# SMPS.net
KiCad netlist of a schematic drawn in EAGLE
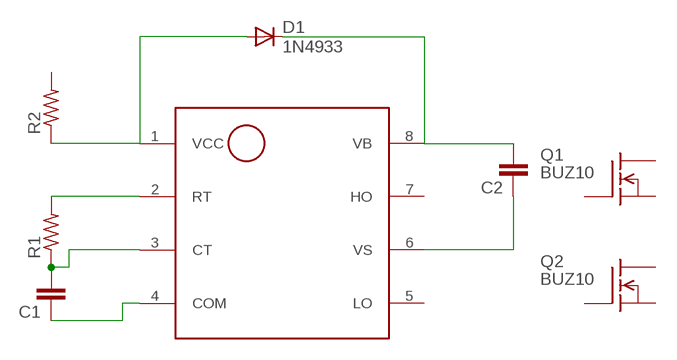
[diagram p0: schematic, sheet 1]

(export (version "E")
  (design (tool "Eeschema 10.0.6"))
  (components
    (comp (ref "C1")
      (value "C-EU025-050X050")
      (footprint "eagle-import:C025-050X050")
      (libsource (lib "eagle-import") (part "C-EU025-050X050"))
    )
    (comp (ref "C2")
      (value "C-EU025-050X050")
      (footprint "eagle-import:C025-050X050")
      (libsource (lib "eagle-import") (part "C-EU025-050X050"))
    )
    (comp (ref "D1")
      (value "1N4933")
      (footprint "eagle-import:DO41-10")
      (libsource (lib "eagle-import") (part "1N4933"))
    )
    (comp (ref "Q1")
      (value "BUZ10")
      (footprint "eagle-import:TO220")
      (libsource (lib "eagle-import") (part "BUZ10"))
    )
    (comp (ref "Q2")
      (value "BUZ10")
      (footprint "eagle-import:TO220")
      (libsource (lib "eagle-import") (part "BUZ10"))
    )
    (comp (ref "R1")
      (value "R-US_0309/10")
      (footprint "eagle-import:0309_10")
      (libsource (lib "eagle-import") (part "R-US_0309/10"))
    )
    (comp (ref "R2")
      (value "R-US_0309/10")
      (footprint "eagle-import:0309_10")
      (libsource (lib "eagle-import") (part "R-US_0309/10"))
    )
    (comp (ref "U$1")
      (value "IRS2153D")
      (footprint "eagle-import:IRS2153D")
      (libsource (lib "eagle-import") (part "IRS2153D"))
    )
  )
  (nets
    (net (code "1") (name "Net-(U$1-COM)") (class "Default")
      (node (ref "C1") (pin "1") (pinfunction "1_1") (pintype "passive"))
      (node (ref "U$1") (pin "4") (pinfunction "COM_4") (pintype "bidirectional"))
    )
    (net (code "2") (name "Net-(U$1-CT)") (class "Default")
      (node (ref "C1") (pin "2") (pinfunction "2_2") (pintype "passive"))
      (node (ref "R1") (pin "1") (pinfunction "1_1") (pintype "passive"))
      (node (ref "U$1") (pin "3") (pinfunction "CT_3") (pintype "bidirectional"))
    )
    (net (code "3") (name "Net-(U$1-RT)") (class "Default")
      (node (ref "R1") (pin "2") (pinfunction "2_2") (pintype "passive"))
      (node (ref "U$1") (pin "2") (pinfunction "RT_2") (pintype "bidirectional"))
    )
    (net (code "4") (name "Net-(U$1-VB)") (class "Default")
      (node (ref "C2") (pin "2") (pinfunction "2_2") (pintype "passive"))
      (node (ref "D1") (pin "C") (pinfunction "C_C") (pintype "passive"))
      (node (ref "U$1") (pin "8") (pinfunction "VB_8") (pintype "bidirectional"))
    )
    (net (code "5") (name "Net-(U$1-VCC)") (class "Default")
      (node (ref "D1") (pin "A") (pinfunction "A_A") (pintype "passive"))
      (node (ref "R2") (pin "1") (pinfunction "1_1") (pintype "passive"))
      (node (ref "U$1") (pin "1") (pinfunction "VCC_1") (pintype "bidirectional"))
    )
    (net (code "6") (name "Net-(U$1-VS)") (class "Default")
      (node (ref "C2") (pin "1") (pinfunction "1_1") (pintype "passive"))
      (node (ref "U$1") (pin "6") (pinfunction "VS_6") (pintype "bidirectional"))
    )
    (net (code "7") (name "unconnected-(Q1-D-Pad2)") (class "Default")
      (node (ref "Q1") (pin "2") (pinfunction "D_2") (pintype "passive"))
    )
    (net (code "8") (name "unconnected-(Q1-G-Pad1)") (class "Default")
      (node (ref "Q1") (pin "1") (pinfunction "G_1") (pintype "passive"))
    )
    (net (code "9") (name "unconnected-(Q1-S-Pad3)") (class "Default")
      (node (ref "Q1") (pin "3") (pinfunction "S_3") (pintype "passive"))
    )
    (net (code "10") (name "unconnected-(Q2-D-Pad2)") (class "Default")
      (node (ref "Q2") (pin "2") (pinfunction "D_2") (pintype "passive"))
    )
    (net (code "11") (name "unconnected-(Q2-G-Pad1)") (class "Default")
      (node (ref "Q2") (pin "1") (pinfunction "G_1") (pintype "passive"))
    )
    (net (code "12") (name "unconnected-(Q2-S-Pad3)") (class "Default")
      (node (ref "Q2") (pin "3") (pinfunction "S_3") (pintype "passive"))
    )
    (net (code "13") (name "unconnected-(R2-Pad2)") (class "Default")
      (node (ref "R2") (pin "2") (pinfunction "2_2") (pintype "passive"))
    )
    (net (code "14") (name "unconnected-(U$1-HO-Pad7)") (class "Default")
      (node (ref "U$1") (pin "7") (pinfunction "HO_7") (pintype "bidirectional"))
    )
    (net (code "15") (name "unconnected-(U$1-LO-Pad5)") (class "Default")
      (node (ref "U$1") (pin "5") (pinfunction "LO_5") (pintype "bidirectional"))
    )
  )
)
